# pcb_main.net
KiCad netlist of a schematic drawn in EasyEDA Pro
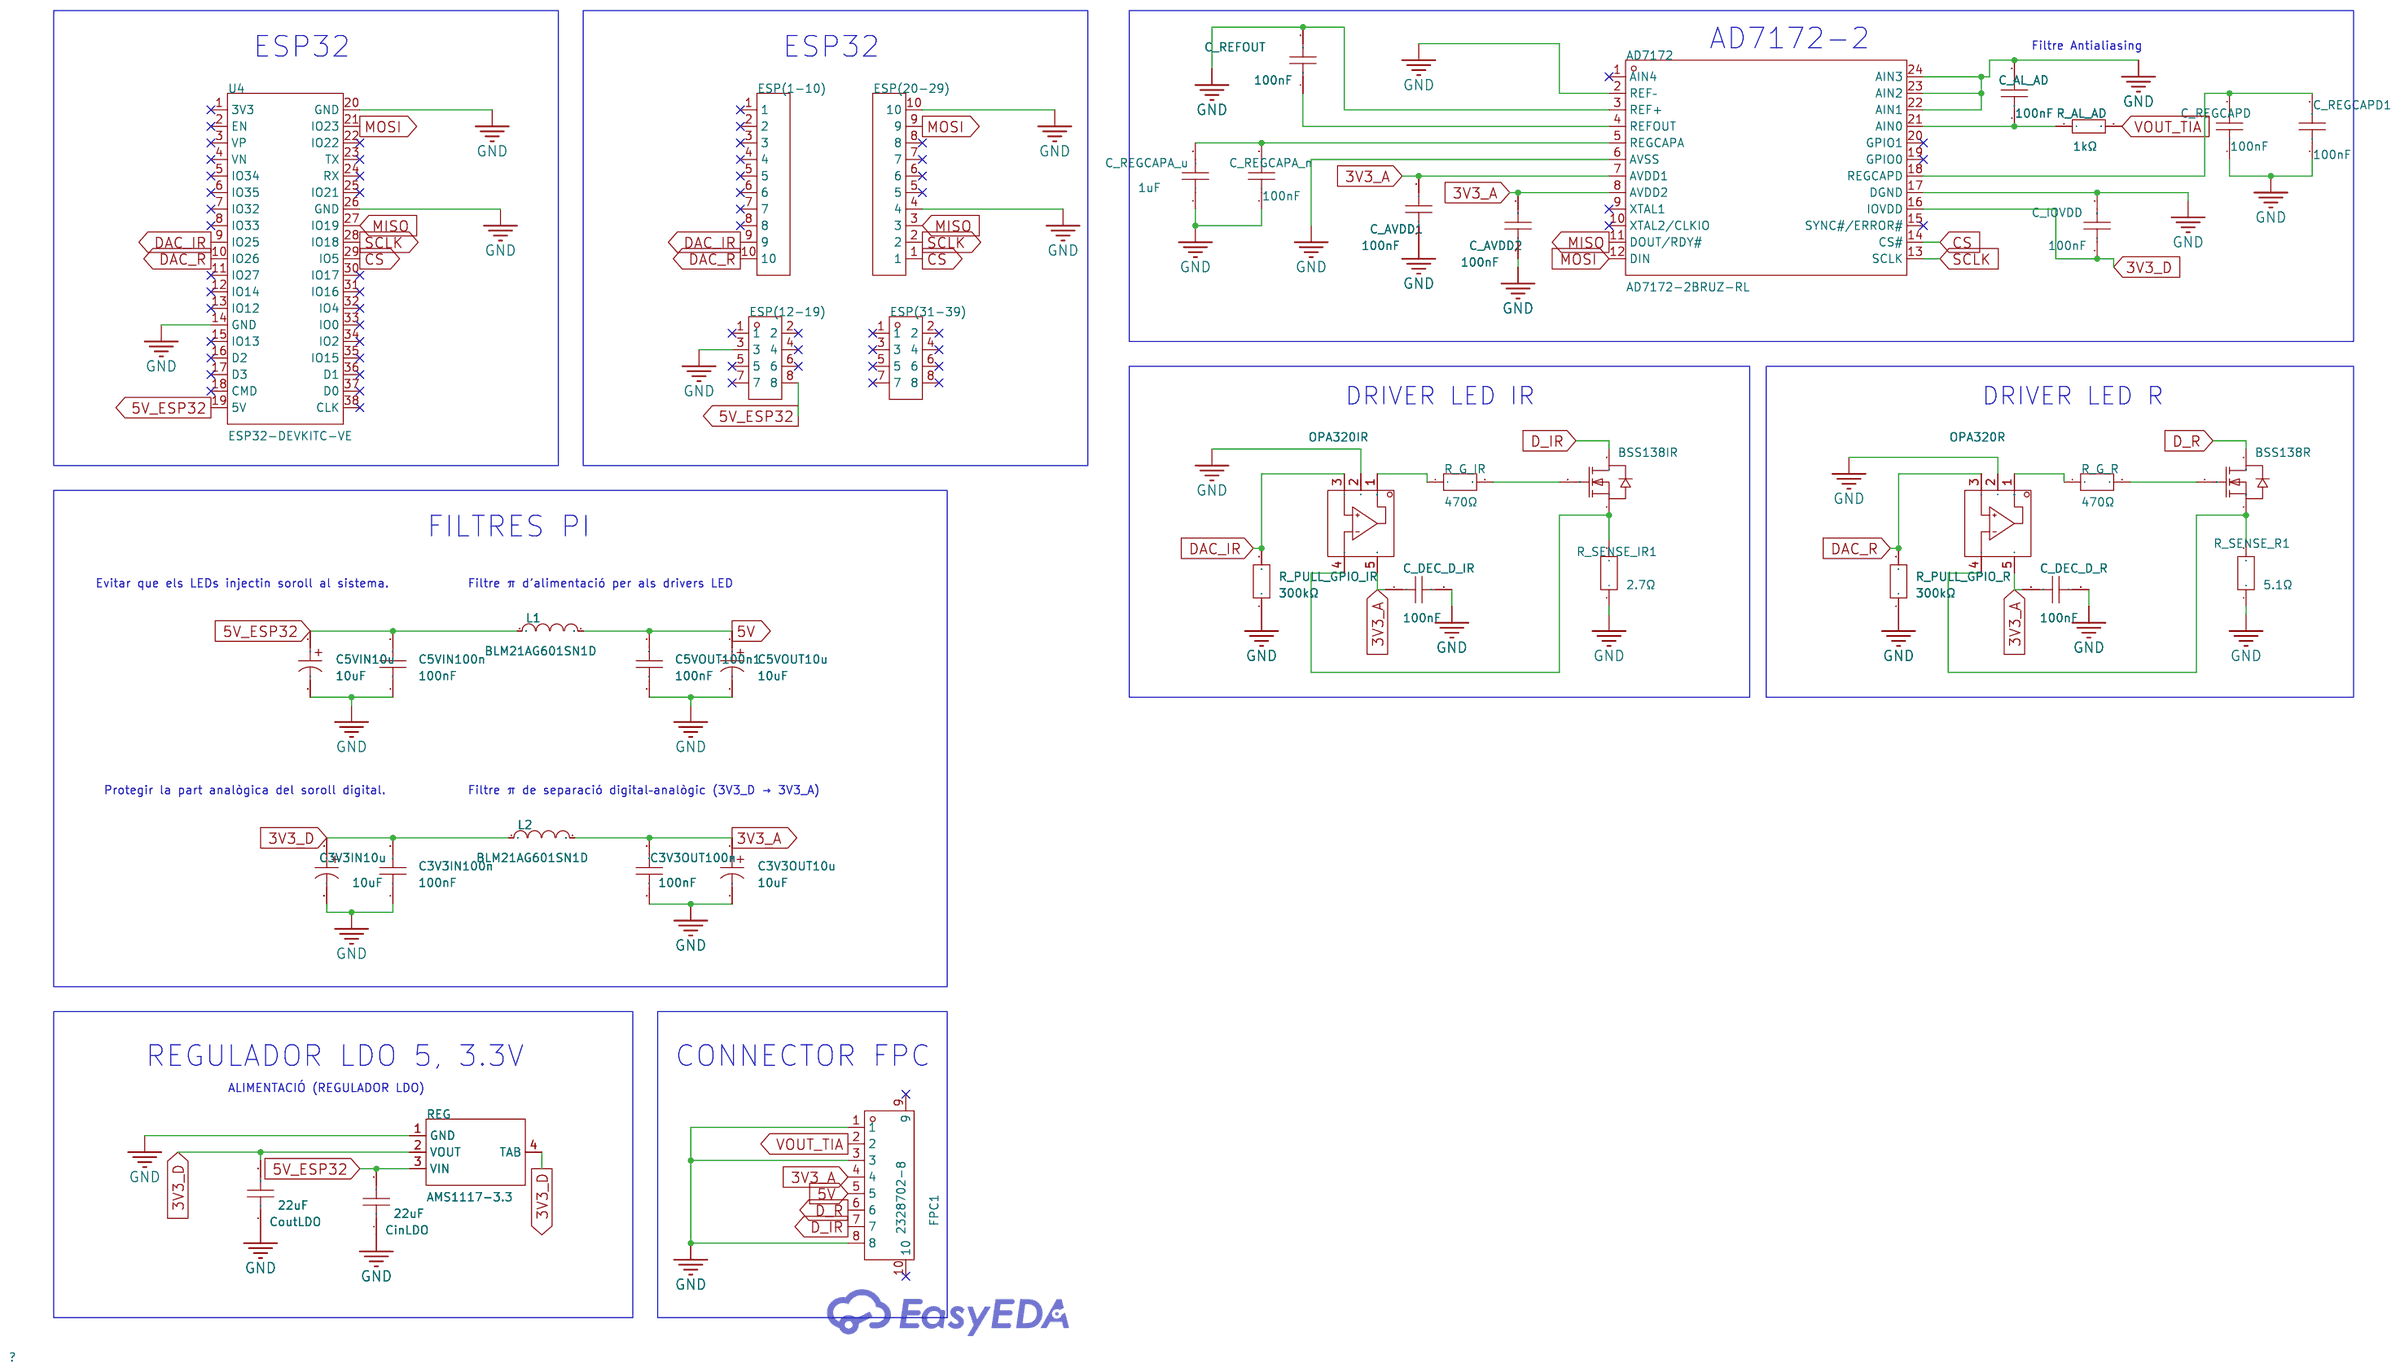
[diagram p0: schematic sheet]

(export (version "E")
  (design (tool "Eeschema 10.0.6"))
  (components
    (comp (ref "AD7172")
      (value "AD7172-2BRUZ-RL")
      (footprint "easyedapro:TSSOP-24_L7.8-W4.4-P0.65-LS6.4-BL_1")
      (fields (field (name "Manufacturer") "ADI(亚德诺)"))
      (libsource (lib "easyedapro") (part "AD7172-2BRUZ-RL"))
    )
    (comp (ref "BSS138IR")
      (value "BSS138IR")
      (footprint "easyedapro:SOT-23-3_L2.9-W1.3-P1.90-LS2.4-BR_1")
      (fields (field (name "Manufacturer") "baocheng(宝乘)"))
      (libsource (lib "easyedapro") (part "BSS138_C51898309"))
    )
    (comp (ref "BSS138R")
      (value "BSS138R")
      (footprint "easyedapro:SOT-23-3_L2.9-W1.3-P1.90-LS2.4-BR_1")
      (fields (field (name "Manufacturer") "baocheng(宝乘)"))
      (libsource (lib "easyedapro") (part "BSS138_C51898309"))
    )
    (comp (ref "C3V3IN10u")
      (value "10uF")
      (footprint "easyedapro:CAP-SMD_BD4.0-L4.3-W4.3-LS5.0-FD")
      (fields (field (name "Manufacturer Part") "RST10UF35V015") (field (name "Manufacturer") "KNSCHA(科尼盛)"))
      (libsource (lib "easyedapro") (part "RST10UF35V015"))
    )
    (comp (ref "C3V3IN100n")
      (value "100nF")
      (footprint "easyedapro:C0603")
      (description "Capacitance:100nF Tolerance:±5% Tolerance:±5% Voltage Rating:16V Temperature Coefficient:-")
      (fields
        (field (name "Manufacturer Part") "0603Y0160104JDR")
        (field (name "Manufacturer") "Knowles(楼氏)")
      )
      (libsource (lib "easyedapro") (part "0603Y0160104JDR"))
    )
    (comp (ref "C3V3OUT10u")
      (value "10uF")
      (footprint "easyedapro:CAP-SMD_BD4.0-L4.3-W4.3-LS5.0-FD")
      (fields (field (name "Manufacturer Part") "RST10UF35V015") (field (name "Manufacturer") "KNSCHA(科尼盛)"))
      (libsource (lib "easyedapro") (part "RST10UF35V015"))
    )
    (comp (ref "C3V3OUT100n")
      (value "100nF")
      (footprint "easyedapro:C0603")
      (description "Capacitance:100nF Tolerance:±5% Tolerance:±5% Voltage Rating:16V Temperature Coefficient:-")
      (fields
        (field (name "Manufacturer Part") "0603Y0160104JDR")
        (field (name "Manufacturer") "Knowles(楼氏)")
      )
      (libsource (lib "easyedapro") (part "0603Y0160104JDR"))
    )
    (comp (ref "C5VIN10u")
      (value "10uF")
      (footprint "easyedapro:CAP-SMD_BD4.0-L4.3-W4.3-LS5.0-FD")
      (fields (field (name "Manufacturer Part") "RST10UF35V015") (field (name "Manufacturer") "KNSCHA(科尼盛)"))
      (libsource (lib "easyedapro") (part "RST10UF35V015"))
    )
    (comp (ref "C5VIN100n")
      (value "100nF")
      (footprint "easyedapro:C0603")
      (description "Capacitance:100nF Tolerance:±5% Tolerance:±5% Voltage Rating:16V Temperature Coefficient:-")
      (fields
        (field (name "Manufacturer Part") "0603Y0160104JDR")
        (field (name "Manufacturer") "Knowles(楼氏)")
      )
      (libsource (lib "easyedapro") (part "0603Y0160104JDR"))
    )
    (comp (ref "C5VOUT10u")
      (value "10uF")
      (footprint "easyedapro:CAP-SMD_BD4.0-L4.3-W4.3-LS5.0-FD")
      (fields (field (name "Manufacturer Part") "RST10UF35V015") (field (name "Manufacturer") "KNSCHA(科尼盛)"))
      (libsource (lib "easyedapro") (part "RST10UF35V015"))
    )
    (comp (ref "C5VOUT100n1")
      (value "100nF")
      (footprint "easyedapro:C0603")
      (description "Capacitance:100nF Tolerance:±5% Tolerance:±5% Voltage Rating:16V Temperature Coefficient:-")
      (fields
        (field (name "Manufacturer Part") "0603Y0160104JDR")
        (field (name "Manufacturer") "Knowles(楼氏)")
      )
      (libsource (lib "easyedapro") (part "0603Y0160104JDR"))
    )
    (comp (ref "CinLDO")
      (value "22uF")
      (footprint "easyedapro:C0805")
      (description "Capacitance:22uF Voltage Rating:10V Temperature Coefficient:X5R")
      (fields
        (field (name "Manufacturer Part") "V226M0805X5R100NHP")
        (field (name "Manufacturer") "VIIYONG(微容)")
      )
      (libsource (lib "easyedapro") (part "V226M0805X5R100NHP"))
    )
    (comp (ref "CoutLDO")
      (value "22uF")
      (footprint "easyedapro:C0805")
      (description "Capacitance:22uF Voltage Rating:10V Temperature Coefficient:X5R")
      (fields
        (field (name "Manufacturer Part") "V226M0805X5R100NHP")
        (field (name "Manufacturer") "VIIYONG(微容)")
      )
      (libsource (lib "easyedapro") (part "V226M0805X5R100NHP"))
    )
    (comp (ref "C_AL_AD")
      (value "100nF")
      (footprint "easyedapro:C0805")
      (description "Capacitance:100nF Tolerance:±10% Tolerance:±10% Voltage Rating:100V Temperature Coefficient:-")
      (fields (field (name "Manufacturer Part") "C0805X104K101TB") (field (name "Manufacturer") "IHHEC(禾伸堂)"))
      (libsource (lib "easyedapro") (part "C0805X104K101TB"))
    )
    (comp (ref "C_AVDD1")
      (value "100nF")
      (footprint "easyedapro:C0603")
      (description "Capacitance:100nF Tolerance:±5% Tolerance:±5% Voltage Rating:16V Temperature Coefficient:-")
      (fields
        (field (name "Manufacturer Part") "0603Y0160104JDR")
        (field (name "Manufacturer") "Knowles(楼氏)")
      )
      (libsource (lib "easyedapro") (part "0603Y0160104JDR"))
    )
    (comp (ref "C_AVDD2")
      (value "100nF")
      (footprint "easyedapro:C0603")
      (description "Capacitance:100nF Tolerance:±5% Tolerance:±5% Voltage Rating:16V Temperature Coefficient:-")
      (fields
        (field (name "Manufacturer Part") "0603Y0160104JDR")
        (field (name "Manufacturer") "Knowles(楼氏)")
      )
      (libsource (lib "easyedapro") (part "0603Y0160104JDR"))
    )
    (comp (ref "C_DEC_D_IR")
      (value "100nF")
      (footprint "easyedapro:C0603")
      (description "Capacitance:100nF Tolerance:±5% Tolerance:±5% Voltage Rating:16V Temperature Coefficient:-")
      (fields
        (field (name "Manufacturer Part") "0603Y0160104JDR")
        (field (name "Manufacturer") "Knowles(楼氏)")
      )
      (libsource (lib "easyedapro") (part "0603Y0160104JDR"))
    )
    (comp (ref "C_DEC_D_R")
      (value "100nF")
      (footprint "easyedapro:C0603")
      (description "Capacitance:100nF Tolerance:±5% Tolerance:±5% Voltage Rating:16V Temperature Coefficient:-")
      (fields
        (field (name "Manufacturer Part") "0603Y0160104JDR")
        (field (name "Manufacturer") "Knowles(楼氏)")
      )
      (libsource (lib "easyedapro") (part "0603Y0160104JDR"))
    )
    (comp (ref "C_IOVDD")
      (value "100nF")
      (footprint "easyedapro:C0603")
      (description "Capacitance:100nF Tolerance:±5% Tolerance:±5% Voltage Rating:16V Temperature Coefficient:-")
      (fields
        (field (name "Manufacturer Part") "0603Y0160104JDR")
        (field (name "Manufacturer") "Knowles(楼氏)")
      )
      (libsource (lib "easyedapro") (part "0603Y0160104JDR"))
    )
    (comp (ref "C_REFOUT")
      (value "100nF")
      (footprint "easyedapro:C0603")
      (description "Capacitance:100nF Tolerance:±5% Tolerance:±5% Voltage Rating:16V Temperature Coefficient:-")
      (fields
        (field (name "Manufacturer Part") "0603Y0160104JDR")
        (field (name "Manufacturer") "Knowles(楼氏)")
      )
      (libsource (lib "easyedapro") (part "0603Y0160104JDR"))
    )
    (comp (ref "C_REGCAPA_n")
      (value "100nF")
      (footprint "easyedapro:C0805")
      (description "Capacitance:100nF Tolerance:±10% Tolerance:±10% Voltage Rating:100V Temperature Coefficient:-")
      (fields (field (name "Manufacturer Part") "C0805X104K101TB") (field (name "Manufacturer") "IHHEC(禾伸堂)"))
      (libsource (lib "easyedapro") (part "C0805X104K101TB"))
    )
    (comp (ref "C_REGCAPA_u")
      (value "1uF")
      (footprint "easyedapro:C0805")
      (description "Capacitance:1uF Tolerance:±10% Tolerance:±10% Voltage Rating:100V")
      (fields
        (field (name "Manufacturer Part") "NC0805B105K101CDDN")
        (field (name "Manufacturer") "HUI JU(汇聚)")
      )
      (libsource (lib "easyedapro") (part "NC0805B105K101CDDN"))
    )
    (comp (ref "C_REGCAPD")
      (value "100nF")
      (footprint "easyedapro:C0805")
      (description "Capacitance:100nF Tolerance:±10% Tolerance:±10% Voltage Rating:100V Temperature Coefficient:-")
      (fields (field (name "Manufacturer Part") "C0805X104K101TB") (field (name "Manufacturer") "IHHEC(禾伸堂)"))
      (libsource (lib "easyedapro") (part "C0805X104K101TB"))
    )
    (comp (ref "C_REGCAPD1")
      (value "100nF")
      (footprint "easyedapro:C0603")
      (description "Capacitance:100nF Tolerance:±5% Tolerance:±5% Voltage Rating:16V Temperature Coefficient:-")
      (fields
        (field (name "Manufacturer Part") "0603Y0160104JDR")
        (field (name "Manufacturer") "Knowles(楼氏)")
      )
      (libsource (lib "easyedapro") (part "0603Y0160104JDR"))
    )
    (comp (ref "ESP(1-10)")
      (value "HX PM2.54-1x10P TP-YQ")
      (footprint "easyedapro:HDR-SMD_10P-P2.54-V-F-LS4.9")
      (fields (field (name "Manufacturer") "hanxia(韩下)"))
      (libsource (lib "easyedapro") (part "HX PM2.54-1X10P TP-YQ"))
    )
    (comp (ref "ESP(12-19)")
      (value "ESP (12-19)")
      (footprint "easyedapro:HDR-SMD_8P-P2.54-V-F-LS4.9")
      (fields (field (name "Manufacturer") "hanxia(韩下)"))
      (libsource (lib "easyedapro") (part "HX PM2.54-1X8P TP-YQ"))
    )
    (comp (ref "ESP(20-29)")
      (value "HX PM2.54-1x10P TP-YQ")
      (footprint "easyedapro:HDR-SMD_10P-P2.54-V-F-LS4.9")
      (fields (field (name "Manufacturer") "hanxia(韩下)"))
      (libsource (lib "easyedapro") (part "HX PM2.54-1X10P TP-YQ"))
    )
    (comp (ref "ESP(31-39)")
      (value "HX PM2.54-1x8P TP-YQ")
      (footprint "easyedapro:HDR-SMD_8P-P2.54-V-F-LS4.9")
      (fields (field (name "Manufacturer") "hanxia(韩下)"))
      (libsource (lib "easyedapro") (part "HX PM2.54-1X8P TP-YQ"))
    )
    (comp (ref "FPC1")
      (value "2328702-8")
      (footprint "easyedapro:CONN-SMD_8P-P0.50-2328702-8")
      (fields (field (name "Manufacturer") "TE Connectivity(泰科电子)"))
      (libsource (lib "easyedapro") (part "2328702-8"))
    )
    (comp (ref "L1")
      (value "BLM21AG601SN1D")
      (footprint "easyedapro:L0805")
      (fields (field (name "Manufacturer") "muRata(村田)"))
      (libsource (lib "easyedapro") (part "BLM21AG601SN1D"))
    )
    (comp (ref "L2")
      (value "BLM21AG601SN1D")
      (footprint "easyedapro:L0805")
      (fields (field (name "Manufacturer") "muRata(村田)"))
      (libsource (lib "easyedapro") (part "BLM21AG601SN1D"))
    )
    (comp (ref "OPA320_D_IR1")
      (value "OPA320IR")
      (footprint "easyedapro:SOT-23-5_L2.9-W1.6-P0.95-LS2.8-BL")
      (fields (field (name "Manufacturer") "TI(德州仪器)"))
      (libsource (lib "easyedapro") (part "OPA320AIDBVT"))
    )
    (comp (ref "OPA320_D_R1")
      (value "OPA320R")
      (footprint "easyedapro:SOT-23-5_L2.9-W1.6-P0.95-LS2.8-BL")
      (fields (field (name "Manufacturer") "TI(德州仪器)"))
      (libsource (lib "easyedapro") (part "OPA320AIDBVT"))
    )
    (comp (ref "REG")
      (value "AMS1117-3.3")
      (footprint "easyedapro:SOT-223-3_L6.5-W3.5-P3.05-LS7.0")
      (fields (field (name "Manufacturer") "TWGMC(迪嘉)"))
      (libsource (lib "easyedapro") (part "AMS1117-3.3_C5250992"))
    )
    (comp (ref "R_AL_AD")
      (value "1kΩ")
      (footprint "easyedapro:R0603")
      (fields (field (name "Manufacturer Part") "RC0603FR-071KL") (field (name "Manufacturer") "YAGEO(国巨)"))
      (libsource (lib "easyedapro") (part "RC0603FR-071KL"))
    )
    (comp (ref "R_G_IR")
      (value "470Ω")
      (footprint "easyedapro:R0603")
      (fields
        (field (name "Manufacturer Part") "CR0603F470RP05Z")
        (field (name "Manufacturer") "EVER OHMS(天二科技)")
      )
      (libsource (lib "easyedapro") (part "CR0603F470RP05Z"))
    )
    (comp (ref "R_G_R")
      (value "470Ω")
      (footprint "easyedapro:R0603")
      (fields
        (field (name "Manufacturer Part") "CR0603F470RP05Z")
        (field (name "Manufacturer") "EVER OHMS(天二科技)")
      )
      (libsource (lib "easyedapro") (part "CR0603F470RP05Z"))
    )
    (comp (ref "R_PULL_GPIO_IR")
      (value "300kΩ")
      (footprint "easyedapro:R0603")
      (fields
        (field (name "Manufacturer Part") "CR0603F300KP05Z")
        (field (name "Manufacturer") "EVER OHMS(天二科技)")
      )
      (libsource (lib "easyedapro") (part "CR0603F300KP05Z"))
    )
    (comp (ref "R_PULL_GPIO_R")
      (value "300kΩ")
      (footprint "easyedapro:R0603")
      (fields
        (field (name "Manufacturer Part") "CR0603F300KP05Z")
        (field (name "Manufacturer") "EVER OHMS(天二科技)")
      )
      (libsource (lib "easyedapro") (part "CR0603F300KP05Z"))
    )
    (comp (ref "R_SENSE_IR1")
      (value "2.7Ω")
      (footprint "easyedapro:R0805")
      (fields
        (field (name "Manufacturer Part") "CR0805F2R70P05S")
        (field (name "Manufacturer") "EVER OHMS(天二科技)")
      )
      (libsource (lib "easyedapro") (part "CR0805F2R70P05S"))
    )
    (comp (ref "R_SENSE_R1")
      (value "5.1Ω")
      (footprint "easyedapro:R0805")
      (fields (field (name "Manufacturer Part") "FRC0805F5R10TS") (field (name "Manufacturer") "FOJAN(富捷)"))
      (libsource (lib "easyedapro") (part "FRC0805F5R10TS"))
    )
    (comp (ref "U4")
      (value "ESP32-DEVKITC-VE")
      (footprint "easyedapro:BULETM-SMD_ESP32-DEVKITC")
      (fields (field (name "Manufacturer") "ESPRESSIF(乐鑫)"))
      (libsource (lib "easyedapro") (part "ESP32-DEVKITC-VE"))
    )
  )
  (nets
    (net (code "1") (name "3V3_A") (class "Default")
      (node (ref "AD7172") (pin "7") (pinfunction "AVDD1_7") (pintype "unspecified"))
      (node (ref "AD7172") (pin "8") (pinfunction "AVDD2_8") (pintype "unspecified"))
      (node (ref "C3V3OUT100n") (pin "2") (pinfunction "2_2") (pintype "unspecified"))
      (node (ref "C3V3OUT10u") (pin "1") (pinfunction "1_1") (pintype "input"))
      (node (ref "C_AVDD1") (pin "2") (pinfunction "2_2") (pintype "unspecified"))
      (node (ref "C_AVDD2") (pin "2") (pinfunction "2_2") (pintype "unspecified"))
      (node (ref "C_DEC_D_IR") (pin "1") (pinfunction "1_1") (pintype "unspecified"))
      (node (ref "C_DEC_D_R") (pin "1") (pinfunction "1_1") (pintype "unspecified"))
      (node (ref "FPC1") (pin "4") (pinfunction "4_4") (pintype "unspecified"))
      (node (ref "L2") (pin "2") (pinfunction "2_2") (pintype "unspecified"))
      (node (ref "OPA320_D_IR1") (pin "5") (pinfunction "V+_5") (pintype "unspecified"))
      (node (ref "OPA320_D_R1") (pin "5") (pinfunction "V+_5") (pintype "unspecified"))
    )
    (net (code "2") (name "3V3_D") (class "Default")
      (node (ref "AD7172") (pin "16") (pinfunction "IOVDD_16") (pintype "unspecified"))
      (node (ref "C3V3IN100n") (pin "2") (pinfunction "2_2") (pintype "unspecified"))
      (node (ref "C3V3IN10u") (pin "1") (pinfunction "1_1") (pintype "input"))
      (node (ref "C_IOVDD") (pin "1") (pinfunction "1_1") (pintype "unspecified"))
      (node (ref "CoutLDO") (pin "2") (pinfunction "2_2") (pintype "unspecified"))
      (node (ref "L2") (pin "1") (pinfunction "1_1") (pintype "unspecified"))
      (node (ref "REG") (pin "2") (pinfunction "VOUT_2") (pintype "unspecified"))
      (node (ref "REG") (pin "4") (pinfunction "TAB_4") (pintype "unspecified"))
    )
    (net (code "3") (name "5V") (class "Default")
      (node (ref "C5VOUT100n1") (pin "2") (pinfunction "2_2") (pintype "unspecified"))
      (node (ref "C5VOUT10u") (pin "1") (pinfunction "1_1") (pintype "input"))
      (node (ref "FPC1") (pin "5") (pinfunction "5_5") (pintype "unspecified"))
      (node (ref "L1") (pin "2") (pinfunction "2_2") (pintype "unspecified"))
    )
    (net (code "4") (name "5V_ESP32") (class "Default")
      (node (ref "C5VIN100n") (pin "2") (pinfunction "2_2") (pintype "unspecified"))
      (node (ref "C5VIN10u") (pin "1") (pinfunction "1_1") (pintype "input"))
      (node (ref "CinLDO") (pin "2") (pinfunction "2_2") (pintype "unspecified"))
      (node (ref "ESP(12-19)") (pin "8") (pinfunction "8_8") (pintype "unspecified"))
      (node (ref "L1") (pin "1") (pinfunction "1_1") (pintype "unspecified"))
      (node (ref "REG") (pin "3") (pinfunction "VIN_3") (pintype "unspecified"))
      (node (ref "U4") (pin "19") (pinfunction "5V_19") (pintype "unspecified"))
    )
    (net (code "5") (name "CS") (class "Default")
      (node (ref "AD7172") (pin "14") (pinfunction "CS#_14") (pintype "unspecified"))
      (node (ref "ESP(20-29)") (pin "1") (pinfunction "1_1") (pintype "unspecified"))
      (node (ref "U4") (pin "29") (pinfunction "IO5_29") (pintype "unspecified"))
    )
    (net (code "6") (name "DAC_IR") (class "Default")
      (node (ref "ESP(1-10)") (pin "9") (pinfunction "9_9") (pintype "unspecified"))
      (node (ref "OPA320_D_IR1") (pin "3") (pinfunction "IN+_3") (pintype "unspecified"))
      (node (ref "R_PULL_GPIO_IR") (pin "2") (pinfunction "2_2") (pintype "unspecified"))
      (node (ref "U4") (pin "9") (pinfunction "IO25_9") (pintype "unspecified"))
    )
    (net (code "7") (name "DAC_R") (class "Default")
      (node (ref "ESP(1-10)") (pin "10") (pinfunction "10_10") (pintype "unspecified"))
      (node (ref "OPA320_D_R1") (pin "3") (pinfunction "IN+_3") (pintype "unspecified"))
      (node (ref "R_PULL_GPIO_R") (pin "2") (pinfunction "2_2") (pintype "unspecified"))
      (node (ref "U4") (pin "10") (pinfunction "IO26_10") (pintype "unspecified"))
    )
    (net (code "8") (name "D_IR") (class "Default")
      (node (ref "BSS138IR") (pin "3") (pinfunction "D_3") (pintype "unspecified"))
      (node (ref "FPC1") (pin "7") (pinfunction "7_7") (pintype "unspecified"))
    )
    (net (code "9") (name "D_R") (class "Default")
      (node (ref "BSS138R") (pin "3") (pinfunction "D_3") (pintype "unspecified"))
      (node (ref "FPC1") (pin "6") (pinfunction "6_6") (pintype "unspecified"))
    )
    (net (code "10") (name "GND") (class "Default")
      (node (ref "AD7172") (pin "17") (pinfunction "DGND_17") (pintype "unspecified"))
      (node (ref "AD7172") (pin "2") (pinfunction "REF–_2") (pintype "unspecified"))
      (node (ref "AD7172") (pin "22") (pinfunction "AIN1_22") (pintype "unspecified"))
      (node (ref "AD7172") (pin "23") (pinfunction "AIN2_23") (pintype "unspecified"))
      (node (ref "AD7172") (pin "24") (pinfunction "AIN3_24") (pintype "unspecified"))
      (node (ref "AD7172") (pin "3") (pinfunction "REF+_3") (pintype "unspecified"))
      (node (ref "AD7172") (pin "6") (pinfunction "AVSS_6") (pintype "unspecified"))
      (node (ref "C3V3IN100n") (pin "1") (pinfunction "1_1") (pintype "unspecified"))
      (node (ref "C3V3IN10u") (pin "2") (pinfunction "2_2") (pintype "input"))
      (node (ref "C3V3OUT100n") (pin "1") (pinfunction "1_1") (pintype "unspecified"))
      (node (ref "C3V3OUT10u") (pin "2") (pinfunction "2_2") (pintype "input"))
      (node (ref "C5VIN100n") (pin "1") (pinfunction "1_1") (pintype "unspecified"))
      (node (ref "C5VIN10u") (pin "2") (pinfunction "2_2") (pintype "input"))
      (node (ref "C5VOUT100n1") (pin "1") (pinfunction "1_1") (pintype "unspecified"))
      (node (ref "C5VOUT10u") (pin "2") (pinfunction "2_2") (pintype "input"))
      (node (ref "C_AL_AD") (pin "2") (pinfunction "2_2") (pintype "input"))
      (node (ref "C_AVDD1") (pin "1") (pinfunction "1_1") (pintype "unspecified"))
      (node (ref "C_AVDD2") (pin "1") (pinfunction "1_1") (pintype "unspecified"))
      (node (ref "C_DEC_D_IR") (pin "2") (pinfunction "2_2") (pintype "unspecified"))
      (node (ref "C_DEC_D_R") (pin "2") (pinfunction "2_2") (pintype "unspecified"))
      (node (ref "C_IOVDD") (pin "2") (pinfunction "2_2") (pintype "unspecified"))
      (node (ref "C_REFOUT") (pin "2") (pinfunction "2_2") (pintype "unspecified"))
      (node (ref "C_REGCAPA_n") (pin "1") (pinfunction "1_1") (pintype "input"))
      (node (ref "C_REGCAPA_u") (pin "1") (pinfunction "1_1") (pintype "unspecified"))
      (node (ref "C_REGCAPD") (pin "1") (pinfunction "1_1") (pintype "input"))
      (node (ref "C_REGCAPD1") (pin "1") (pinfunction "1_1") (pintype "unspecified"))
      (node (ref "CinLDO") (pin "1") (pinfunction "1_1") (pintype "unspecified"))
      (node (ref "CoutLDO") (pin "1") (pinfunction "1_1") (pintype "unspecified"))
      (node (ref "ESP(12-19)") (pin "3") (pinfunction "3_3") (pintype "unspecified"))
      (node (ref "ESP(20-29)") (pin "10") (pinfunction "10_10") (pintype "unspecified"))
      (node (ref "ESP(20-29)") (pin "4") (pinfunction "4_4") (pintype "unspecified"))
      (node (ref "FPC1") (pin "1") (pinfunction "1_1") (pintype "unspecified"))
      (node (ref "FPC1") (pin "3") (pinfunction "3_3") (pintype "unspecified"))
      (node (ref "FPC1") (pin "8") (pinfunction "8_8") (pintype "unspecified"))
      (node (ref "OPA320_D_IR1") (pin "2") (pinfunction "V-_2") (pintype "unspecified"))
      (node (ref "OPA320_D_R1") (pin "2") (pinfunction "V-_2") (pintype "unspecified"))
      (node (ref "REG") (pin "1") (pinfunction "GND_1") (pintype "unspecified"))
      (node (ref "R_PULL_GPIO_IR") (pin "1") (pinfunction "1_1") (pintype "unspecified"))
      (node (ref "R_PULL_GPIO_R") (pin "1") (pinfunction "1_1") (pintype "unspecified"))
      (node (ref "R_SENSE_IR1") (pin "1") (pinfunction "1_1") (pintype "unspecified"))
      (node (ref "R_SENSE_R1") (pin "1") (pinfunction "1_1") (pintype "unspecified"))
      (node (ref "U4") (pin "14") (pinfunction "GND_14") (pintype "unspecified"))
      (node (ref "U4") (pin "20") (pinfunction "GND_20") (pintype "unspecified"))
      (node (ref "U4") (pin "26") (pinfunction "GND_26") (pintype "unspecified"))
    )
    (net (code "11") (name "MISO") (class "Default")
      (node (ref "AD7172") (pin "11") (pinfunction "DOUT/RDY#_11") (pintype "unspecified"))
      (node (ref "ESP(20-29)") (pin "3") (pinfunction "3_3") (pintype "unspecified"))
      (node (ref "U4") (pin "27") (pinfunction "IO19_27") (pintype "unspecified"))
    )
    (net (code "12") (name "MOSI") (class "Default")
      (node (ref "AD7172") (pin "12") (pinfunction "DIN_12") (pintype "unspecified"))
      (node (ref "ESP(20-29)") (pin "9") (pinfunction "9_9") (pintype "unspecified"))
      (node (ref "U4") (pin "21") (pinfunction "IO23_21") (pintype "unspecified"))
    )
    (net (code "13") (name "Net-(AD7172-AIN0)") (class "Default")
      (node (ref "AD7172") (pin "21") (pinfunction "AIN0_21") (pintype "unspecified"))
      (node (ref "C_AL_AD") (pin "1") (pinfunction "1_1") (pintype "input"))
      (node (ref "R_AL_AD") (pin "1") (pinfunction "1_1") (pintype "input"))
    )
    (net (code "14") (name "Net-(AD7172-REFOUT)") (class "Default")
      (node (ref "AD7172") (pin "4") (pinfunction "REFOUT_4") (pintype "unspecified"))
      (node (ref "C_REFOUT") (pin "1") (pinfunction "1_1") (pintype "unspecified"))
    )
    (net (code "15") (name "Net-(AD7172-REGCAPA)") (class "Default")
      (node (ref "AD7172") (pin "5") (pinfunction "REGCAPA_5") (pintype "unspecified"))
      (node (ref "C_REGCAPA_n") (pin "2") (pinfunction "2_2") (pintype "input"))
      (node (ref "C_REGCAPA_u") (pin "2") (pinfunction "2_2") (pintype "unspecified"))
    )
    (net (code "16") (name "Net-(AD7172-REGCAPD)") (class "Default")
      (node (ref "AD7172") (pin "18") (pinfunction "REGCAPD_18") (pintype "unspecified"))
      (node (ref "C_REGCAPD") (pin "2") (pinfunction "2_2") (pintype "input"))
      (node (ref "C_REGCAPD1") (pin "2") (pinfunction "2_2") (pintype "unspecified"))
    )
    (net (code "17") (name "Net-(BSS138IR-G)") (class "Default")
      (node (ref "BSS138IR") (pin "1") (pinfunction "G_1") (pintype "unspecified"))
      (node (ref "R_G_IR") (pin "2") (pinfunction "2_2") (pintype "unspecified"))
    )
    (net (code "18") (name "Net-(BSS138IR-S)") (class "Default")
      (node (ref "BSS138IR") (pin "2") (pinfunction "S_2") (pintype "unspecified"))
      (node (ref "OPA320_D_IR1") (pin "4") (pinfunction "IN-_4") (pintype "unspecified"))
      (node (ref "R_SENSE_IR1") (pin "2") (pinfunction "2_2") (pintype "unspecified"))
    )
    (net (code "19") (name "Net-(BSS138R-G)") (class "Default")
      (node (ref "BSS138R") (pin "1") (pinfunction "G_1") (pintype "unspecified"))
      (node (ref "R_G_R") (pin "2") (pinfunction "2_2") (pintype "unspecified"))
    )
    (net (code "20") (name "Net-(BSS138R-S)") (class "Default")
      (node (ref "BSS138R") (pin "2") (pinfunction "S_2") (pintype "unspecified"))
      (node (ref "OPA320_D_R1") (pin "4") (pinfunction "IN-_4") (pintype "unspecified"))
      (node (ref "R_SENSE_R1") (pin "2") (pinfunction "2_2") (pintype "unspecified"))
    )
    (net (code "21") (name "Net-(OPA320_D_IR1-OUT)") (class "Default")
      (node (ref "OPA320_D_IR1") (pin "1") (pinfunction "OUT_1") (pintype "unspecified"))
      (node (ref "R_G_IR") (pin "1") (pinfunction "1_1") (pintype "unspecified"))
    )
    (net (code "22") (name "Net-(OPA320_D_R1-OUT)") (class "Default")
      (node (ref "OPA320_D_R1") (pin "1") (pinfunction "OUT_1") (pintype "unspecified"))
      (node (ref "R_G_R") (pin "1") (pinfunction "1_1") (pintype "unspecified"))
    )
    (net (code "23") (name "SCLK") (class "Default")
      (node (ref "AD7172") (pin "13") (pinfunction "SCLK_13") (pintype "unspecified"))
      (node (ref "ESP(20-29)") (pin "2") (pinfunction "2_2") (pintype "unspecified"))
      (node (ref "U4") (pin "28") (pinfunction "IO18_28") (pintype "unspecified"))
    )
    (net (code "24") (name "VOUT_TIA") (class "Default")
      (node (ref "FPC1") (pin "2") (pinfunction "2_2") (pintype "unspecified"))
      (node (ref "R_AL_AD") (pin "2") (pinfunction "2_2") (pintype "input"))
    )
    (net (code "25") (name "unconnected-(AD7172-AIN4-Pad1)") (class "Default")
      (node (ref "AD7172") (pin "1") (pinfunction "AIN4_1") (pintype "unspecified+no_connect"))
    )
    (net (code "26") (name "unconnected-(AD7172-GPIO0-Pad19)") (class "Default")
      (node (ref "AD7172") (pin "19") (pinfunction "GPIO0_19") (pintype "unspecified+no_connect"))
    )
    (net (code "27") (name "unconnected-(AD7172-GPIO1-Pad20)") (class "Default")
      (node (ref "AD7172") (pin "20") (pinfunction "GPIO1_20") (pintype "unspecified+no_connect"))
    )
    (net (code "28") (name "unconnected-(AD7172-SYNC#{slash}ERROR#-Pad15)") (class "Default")
      (node (ref "AD7172") (pin "15") (pinfunction "SYNC#/ERROR#_15") (pintype "unspecified+no_connect"))
    )
    (net (code "29") (name "unconnected-(AD7172-XTAL1-Pad9)") (class "Default")
      (node (ref "AD7172") (pin "9") (pinfunction "XTAL1_9") (pintype "unspecified+no_connect"))
    )
    (net (code "30") (name "unconnected-(AD7172-XTAL2{slash}CLKIO-Pad10)") (class "Default")
      (node (ref "AD7172") (pin "10") (pinfunction "XTAL2/CLKIO_10") (pintype "unspecified+no_connect"))
    )
    (net (code "31") (name "unconnected-(ESP(1-10)-Pad1)") (class "Default")
      (node (ref "ESP(1-10)") (pin "1") (pinfunction "1_1") (pintype "unspecified+no_connect"))
    )
    (net (code "32") (name "unconnected-(ESP(1-10)-Pad2)") (class "Default")
      (node (ref "ESP(1-10)") (pin "2") (pinfunction "2_2") (pintype "unspecified+no_connect"))
    )
    (net (code "33") (name "unconnected-(ESP(1-10)-Pad3)") (class "Default")
      (node (ref "ESP(1-10)") (pin "3") (pinfunction "3_3") (pintype "unspecified+no_connect"))
    )
    (net (code "34") (name "unconnected-(ESP(1-10)-Pad4)") (class "Default")
      (node (ref "ESP(1-10)") (pin "4") (pinfunction "4_4") (pintype "unspecified+no_connect"))
    )
    (net (code "35") (name "unconnected-(ESP(1-10)-Pad5)") (class "Default")
      (node (ref "ESP(1-10)") (pin "5") (pinfunction "5_5") (pintype "unspecified+no_connect"))
    )
    (net (code "36") (name "unconnected-(ESP(1-10)-Pad6)") (class "Default")
      (node (ref "ESP(1-10)") (pin "6") (pinfunction "6_6") (pintype "unspecified+no_connect"))
    )
    (net (code "37") (name "unconnected-(ESP(1-10)-Pad7)") (class "Default")
      (node (ref "ESP(1-10)") (pin "7") (pinfunction "7_7") (pintype "unspecified+no_connect"))
    )
    (net (code "38") (name "unconnected-(ESP(1-10)-Pad8)") (class "Default")
      (node (ref "ESP(1-10)") (pin "8") (pinfunction "8_8") (pintype "unspecified+no_connect"))
    )
    (net (code "39") (name "unconnected-(ESP(12-19)-Pad1)") (class "Default")
      (node (ref "ESP(12-19)") (pin "1") (pinfunction "1_1") (pintype "unspecified+no_connect"))
    )
    (net (code "40") (name "unconnected-(ESP(12-19)-Pad2)") (class "Default")
      (node (ref "ESP(12-19)") (pin "2") (pinfunction "2_2") (pintype "unspecified+no_connect"))
    )
    (net (code "41") (name "unconnected-(ESP(12-19)-Pad4)") (class "Default")
      (node (ref "ESP(12-19)") (pin "4") (pinfunction "4_4") (pintype "unspecified+no_connect"))
    )
    (net (code "42") (name "unconnected-(ESP(12-19)-Pad5)") (class "Default")
      (node (ref "ESP(12-19)") (pin "5") (pinfunction "5_5") (pintype "unspecified+no_connect"))
    )
    (net (code "43") (name "unconnected-(ESP(12-19)-Pad6)") (class "Default")
      (node (ref "ESP(12-19)") (pin "6") (pinfunction "6_6") (pintype "unspecified+no_connect"))
    )
    (net (code "44") (name "unconnected-(ESP(12-19)-Pad7)") (class "Default")
      (node (ref "ESP(12-19)") (pin "7") (pinfunction "7_7") (pintype "unspecified+no_connect"))
    )
    (net (code "45") (name "unconnected-(ESP(20-29)-Pad5)") (class "Default")
      (node (ref "ESP(20-29)") (pin "5") (pinfunction "5_5") (pintype "unspecified+no_connect"))
    )
    (net (code "46") (name "unconnected-(ESP(20-29)-Pad6)") (class "Default")
      (node (ref "ESP(20-29)") (pin "6") (pinfunction "6_6") (pintype "unspecified+no_connect"))
    )
    (net (code "47") (name "unconnected-(ESP(20-29)-Pad7)") (class "Default")
      (node (ref "ESP(20-29)") (pin "7") (pinfunction "7_7") (pintype "unspecified+no_connect"))
    )
    (net (code "48") (name "unconnected-(ESP(20-29)-Pad8)") (class "Default")
      (node (ref "ESP(20-29)") (pin "8") (pinfunction "8_8") (pintype "unspecified+no_connect"))
    )
    (net (code "49") (name "unconnected-(ESP(31-39)-Pad1)") (class "Default")
      (node (ref "ESP(31-39)") (pin "1") (pinfunction "1_1") (pintype "unspecified+no_connect"))
    )
    (net (code "50") (name "unconnected-(ESP(31-39)-Pad2)") (class "Default")
      (node (ref "ESP(31-39)") (pin "2") (pinfunction "2_2") (pintype "unspecified+no_connect"))
    )
    (net (code "51") (name "unconnected-(ESP(31-39)-Pad3)") (class "Default")
      (node (ref "ESP(31-39)") (pin "3") (pinfunction "3_3") (pintype "unspecified+no_connect"))
    )
    (net (code "52") (name "unconnected-(ESP(31-39)-Pad4)") (class "Default")
      (node (ref "ESP(31-39)") (pin "4") (pinfunction "4_4") (pintype "unspecified+no_connect"))
    )
    (net (code "53") (name "unconnected-(ESP(31-39)-Pad5)") (class "Default")
      (node (ref "ESP(31-39)") (pin "5") (pinfunction "5_5") (pintype "unspecified+no_connect"))
    )
    (net (code "54") (name "unconnected-(ESP(31-39)-Pad6)") (class "Default")
      (node (ref "ESP(31-39)") (pin "6") (pinfunction "6_6") (pintype "unspecified+no_connect"))
    )
    (net (code "55") (name "unconnected-(ESP(31-39)-Pad7)") (class "Default")
      (node (ref "ESP(31-39)") (pin "7") (pinfunction "7_7") (pintype "unspecified+no_connect"))
    )
    (net (code "56") (name "unconnected-(ESP(31-39)-Pad8)") (class "Default")
      (node (ref "ESP(31-39)") (pin "8") (pinfunction "8_8") (pintype "unspecified+no_connect"))
    )
    (net (code "57") (name "unconnected-(FPC1-Pad9)") (class "Default")
      (node (ref "FPC1") (pin "9") (pinfunction "9_9") (pintype "unspecified+no_connect"))
    )
    (net (code "58") (name "unconnected-(FPC1-Pad10)") (class "Default")
      (node (ref "FPC1") (pin "10") (pinfunction "10_10") (pintype "unspecified+no_connect"))
    )
    (net (code "59") (name "unconnected-(U4-3V3-Pad1)") (class "Default")
      (node (ref "U4") (pin "1") (pinfunction "3V3_1") (pintype "unspecified+no_connect"))
    )
    (net (code "60") (name "unconnected-(U4-CLK-Pad38)") (class "Default")
      (node (ref "U4") (pin "38") (pinfunction "CLK_38") (pintype "unspecified+no_connect"))
    )
    (net (code "61") (name "unconnected-(U4-CMD-Pad18)") (class "Default")
      (node (ref "U4") (pin "18") (pinfunction "CMD_18") (pintype "unspecified+no_connect"))
    )
    (net (code "62") (name "unconnected-(U4-D0-Pad37)") (class "Default")
      (node (ref "U4") (pin "37") (pinfunction "D0_37") (pintype "unspecified+no_connect"))
    )
    (net (code "63") (name "unconnected-(U4-D1-Pad36)") (class "Default")
      (node (ref "U4") (pin "36") (pinfunction "D1_36") (pintype "unspecified+no_connect"))
    )
    (net (code "64") (name "unconnected-(U4-D2-Pad16)") (class "Default")
      (node (ref "U4") (pin "16") (pinfunction "D2_16") (pintype "unspecified+no_connect"))
    )
    (net (code "65") (name "unconnected-(U4-D3-Pad17)") (class "Default")
      (node (ref "U4") (pin "17") (pinfunction "D3_17") (pintype "unspecified+no_connect"))
    )
    (net (code "66") (name "unconnected-(U4-EN-Pad2)") (class "Default")
      (node (ref "U4") (pin "2") (pinfunction "EN_2") (pintype "unspecified+no_connect"))
    )
    (net (code "67") (name "unconnected-(U4-IO0-Pad33)") (class "Default")
      (node (ref "U4") (pin "33") (pinfunction "IO0_33") (pintype "unspecified+no_connect"))
    )
    (net (code "68") (name "unconnected-(U4-IO2-Pad34)") (class "Default")
      (node (ref "U4") (pin "34") (pinfunction "IO2_34") (pintype "unspecified+no_connect"))
    )
    (net (code "69") (name "unconnected-(U4-IO4-Pad32)") (class "Default")
      (node (ref "U4") (pin "32") (pinfunction "IO4_32") (pintype "unspecified+no_connect"))
    )
    (net (code "70") (name "unconnected-(U4-IO12-Pad13)") (class "Default")
      (node (ref "U4") (pin "13") (pinfunction "IO12_13") (pintype "unspecified+no_connect"))
    )
    (net (code "71") (name "unconnected-(U4-IO13-Pad15)") (class "Default")
      (node (ref "U4") (pin "15") (pinfunction "IO13_15") (pintype "unspecified+no_connect"))
    )
    (net (code "72") (name "unconnected-(U4-IO14-Pad12)") (class "Default")
      (node (ref "U4") (pin "12") (pinfunction "IO14_12") (pintype "unspecified+no_connect"))
    )
    (net (code "73") (name "unconnected-(U4-IO15-Pad35)") (class "Default")
      (node (ref "U4") (pin "35") (pinfunction "IO15_35") (pintype "unspecified+no_connect"))
    )
    (net (code "74") (name "unconnected-(U4-IO16-Pad31)") (class "Default")
      (node (ref "U4") (pin "31") (pinfunction "IO16_31") (pintype "unspecified+no_connect"))
    )
    (net (code "75") (name "unconnected-(U4-IO17-Pad30)") (class "Default")
      (node (ref "U4") (pin "30") (pinfunction "IO17_30") (pintype "unspecified+no_connect"))
    )
    (net (code "76") (name "unconnected-(U4-IO21-Pad25)") (class "Default")
      (node (ref "U4") (pin "25") (pinfunction "IO21_25") (pintype "unspecified+no_connect"))
    )
    (net (code "77") (name "unconnected-(U4-IO22-Pad22)") (class "Default")
      (node (ref "U4") (pin "22") (pinfunction "IO22_22") (pintype "unspecified+no_connect"))
    )
    (net (code "78") (name "unconnected-(U4-IO27-Pad11)") (class "Default")
      (node (ref "U4") (pin "11") (pinfunction "IO27_11") (pintype "unspecified+no_connect"))
    )
    (net (code "79") (name "unconnected-(U4-IO32-Pad7)") (class "Default")
      (node (ref "U4") (pin "7") (pinfunction "IO32_7") (pintype "unspecified+no_connect"))
    )
    (net (code "80") (name "unconnected-(U4-IO33-Pad8)") (class "Default")
      (node (ref "U4") (pin "8") (pinfunction "IO33_8") (pintype "unspecified+no_connect"))
    )
    (net (code "81") (name "unconnected-(U4-IO34-Pad5)") (class "Default")
      (node (ref "U4") (pin "5") (pinfunction "IO34_5") (pintype "unspecified+no_connect"))
    )
    (net (code "82") (name "unconnected-(U4-IO35-Pad6)") (class "Default")
      (node (ref "U4") (pin "6") (pinfunction "IO35_6") (pintype "unspecified+no_connect"))
    )
    (net (code "83") (name "unconnected-(U4-RX-Pad24)") (class "Default")
      (node (ref "U4") (pin "24") (pinfunction "RX_24") (pintype "unspecified+no_connect"))
    )
    (net (code "84") (name "unconnected-(U4-TX-Pad23)") (class "Default")
      (node (ref "U4") (pin "23") (pinfunction "TX_23") (pintype "unspecified+no_connect"))
    )
    (net (code "85") (name "unconnected-(U4-VN-Pad4)") (class "Default")
      (node (ref "U4") (pin "4") (pinfunction "VN_4") (pintype "unspecified+no_connect"))
    )
    (net (code "86") (name "unconnected-(U4-VP-Pad3)") (class "Default")
      (node (ref "U4") (pin "3") (pinfunction "VP_3") (pintype "unspecified+no_connect"))
    )
  )
)
